# Main.net
KiCad netlist of a schematic drawn in Altium Designer
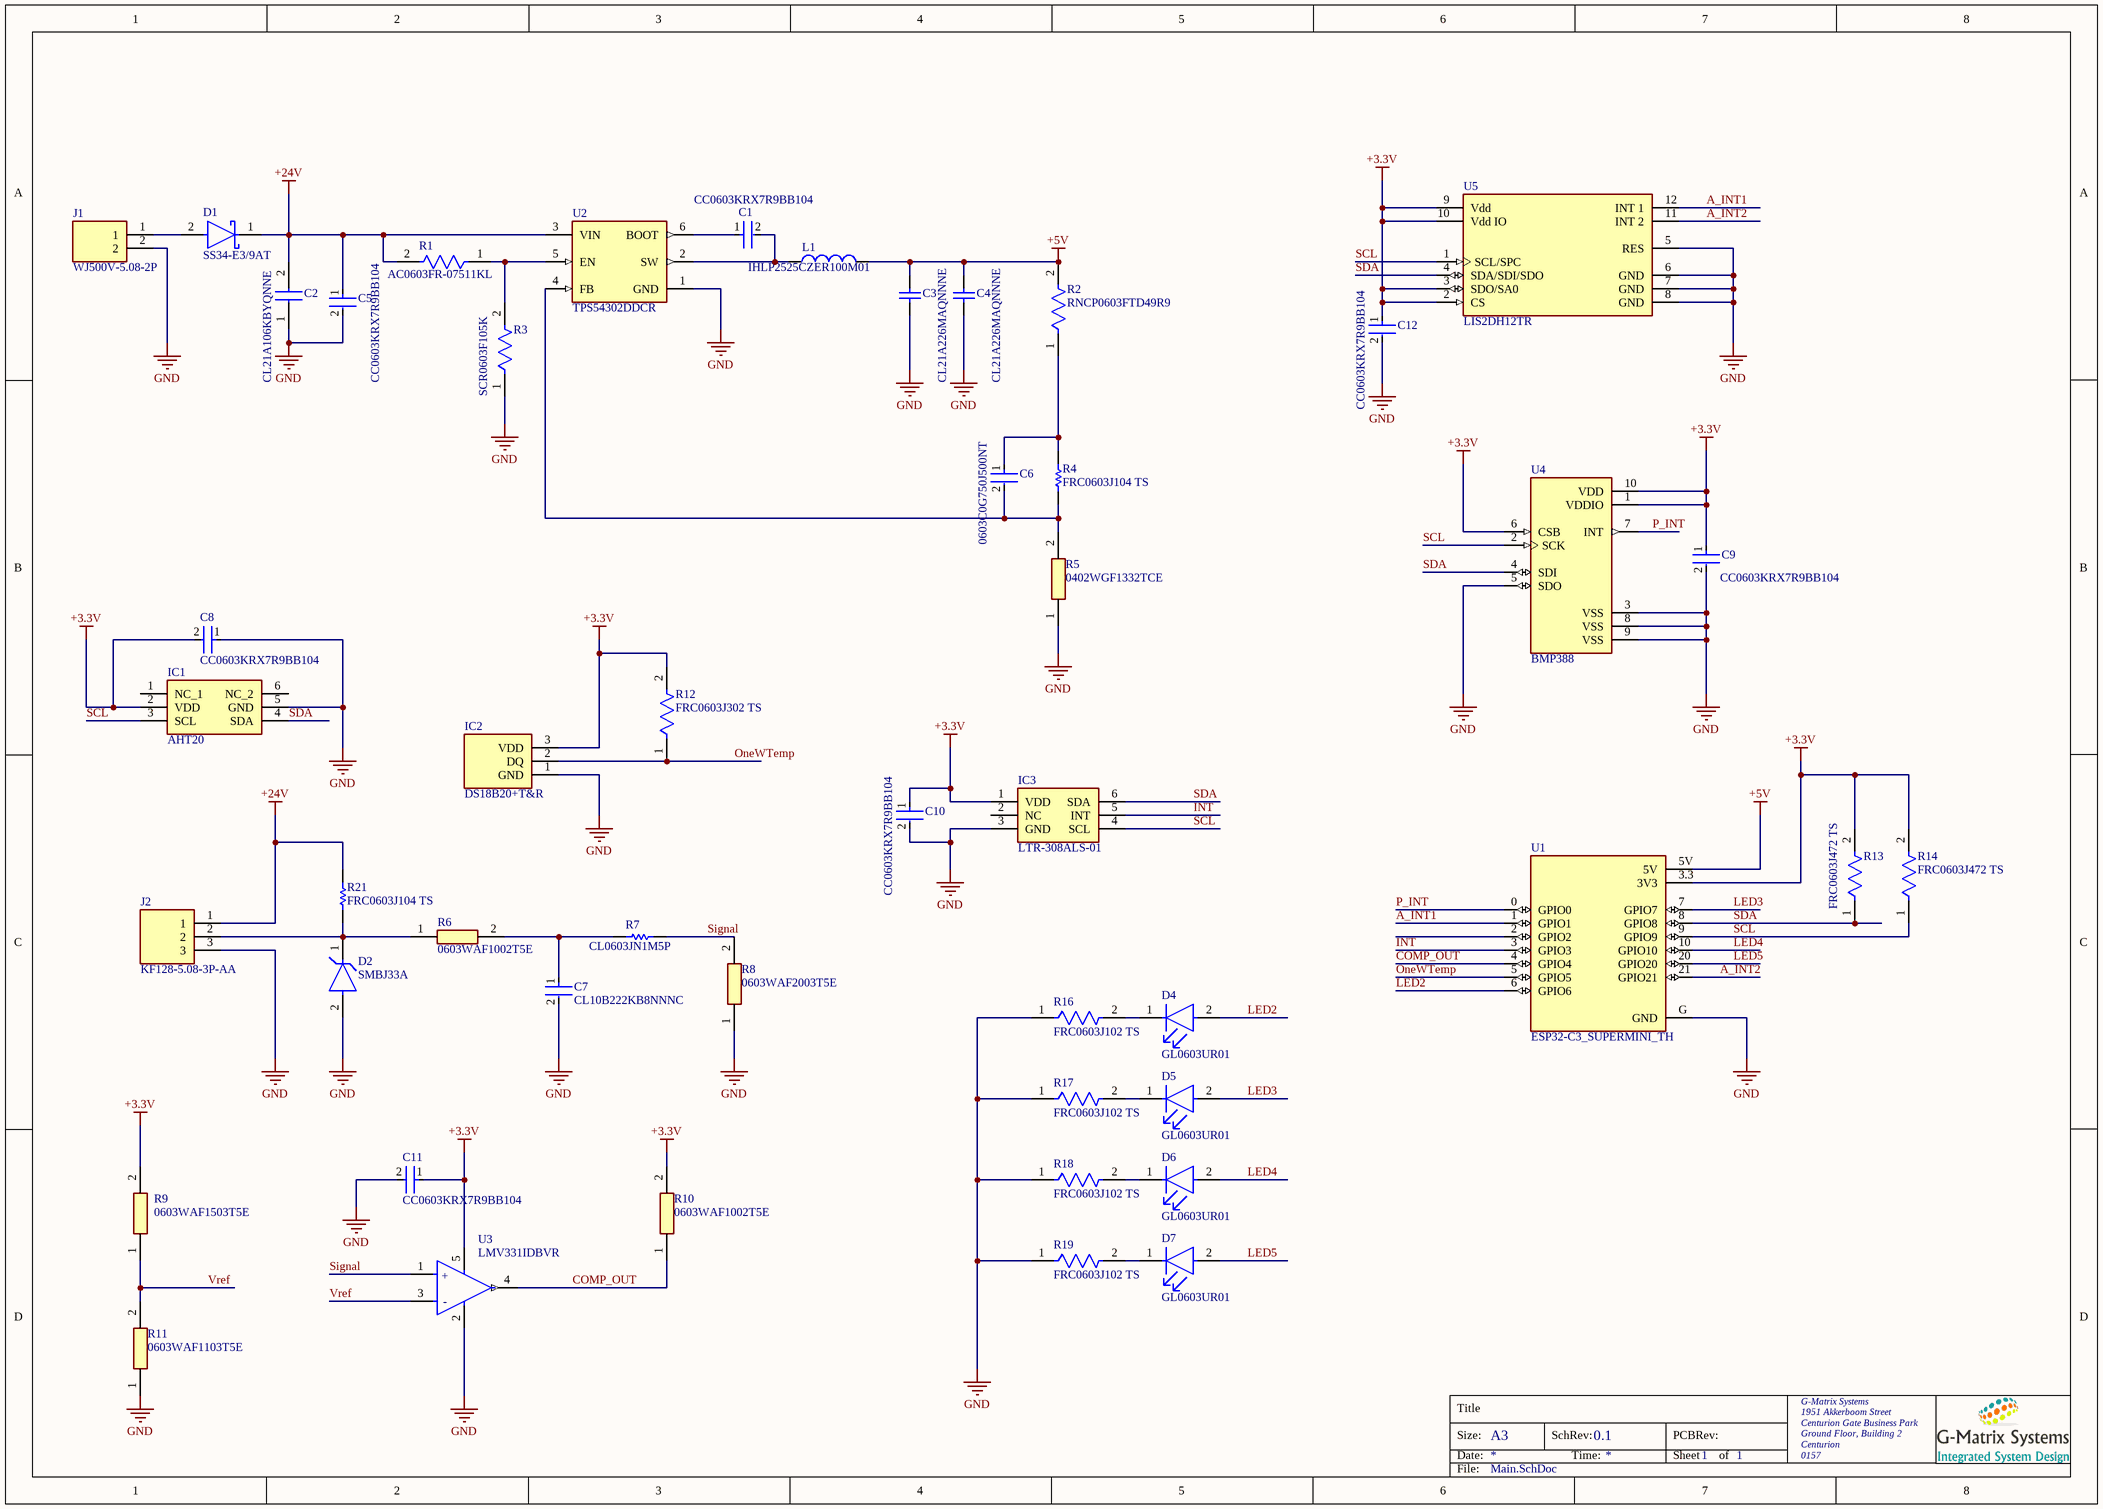
[diagram p0: Main.SchDoc]

(export (version "E")
  (design (tool "Eeschema 10.0.6"))
  (components
    (comp (ref "C1")
      (value "CC0603KRX7R9BB104")
      (footprint "FP-CC0603-DA-MFG")
      (description "CAP CER 0.1UF 50V X7R 0603")
      (fields (field (name "MANUFACTURER") "YAGEO") (field (name "VOLTAGE") "50 V"))
      (libsource (lib "Altium Content Vault") (part "11868f565c42a9108669ba33697ecf6"))
    )
    (comp (ref "C2")
      (value "CL21A106KBYQNNE")
      (footprint "SamacSys:CAPC2012X145N")
      (description "Capacitor")
      (fields (field (name "MOUSER PART NUMBER") "187-CL21A106KBYQNNE"))
      (libsource (lib "*") (part "CL21A106KBYQNNE"))
    )
    (comp (ref "C3")
      (value "CL21A226MAQNNNE")
      (footprint "CAPC2013X140X45LL15T25")
      (description "Multi-layer Ceramic Capacitor, 22 uF, -55 to 85 degC, 2-Pin SMD (0805), RoHS, Tape and Reel")
      (fields (field (name "MANUFACTURER") "Samsung Electro-Mechanics") (field (name "TOLERANCE") "±20%"))
      (libsource (lib "Altium Content Vault") (part "CAP-NP-2"))
    )
    (comp (ref "C4")
      (value "CL21A226MAQNNNE")
      (footprint "CAPC2013X140X45LL15T25")
      (description "Multi-layer Ceramic Capacitor, 22 uF, -55 to 85 degC, 2-Pin SMD (0805), RoHS, Tape and Reel")
      (fields (field (name "MANUFACTURER") "Samsung Electro-Mechanics") (field (name "TOLERANCE") "±20%"))
      (libsource (lib "Altium Content Vault") (part "CAP-NP-2"))
    )
    (comp (ref "C5")
      (value "CC0603KRX7R9BB104")
      (footprint "FP-CC0603-DA-MFG")
      (description "CAP CER 0.1UF 50V X7R 0603")
      (fields (field (name "MANUFACTURER") "YAGEO") (field (name "VOLTAGE") "50 V"))
      (libsource (lib "Altium Content Vault") (part "11868f565c42a9108669ba33697ecf6"))
    )
    (comp (ref "C6")
      (value "0603C0G750J500NT")
      (footprint "FP-CC0603-0_1-0_9-MFG")
      (description "CC0603FRNPO9BN750 Multilayer Ceramic Capacitor, 75 pF, 50 V, ± 1%, C0G (NP0), 0603 [1608 Metric]")
      (fields (field (name "TOLERANCE") "1%"))
      (libsource (lib "Altium Content Vault") (part "b4654b650e69147ec39a6b967a45e02"))
    )
    (comp (ref "C7")
      (value "CL10B222KB8NNNC")
      (footprint "FP-CL10-IPC_A")
      (description "Cap Ceramic 2.2nF 50V X7R ±10% Pad SMD 0603 +125°C T/R")
      (fields (field (name "VOLTAGE") "25V") (field (name "TOLERANCE") "10%"))
      (libsource (lib "Altium Content Vault") (part "b4654b650e69147ec39a6b967a45e02"))
    )
    (comp (ref "C8")
      (value "CC0603KRX7R9BB104")
      (footprint "FP-CC0603-DA-MFG")
      (description "CAP CER 0.1UF 50V X7R 0603")
      (fields (field (name "MANUFACTURER") "YAGEO") (field (name "VOLTAGE") "50 V"))
      (libsource (lib "Altium Content Vault") (part "11868f565c42a9108669ba33697ecf6"))
    )
    (comp (ref "C9")
      (value "CC0603KRX7R9BB104")
      (footprint "FP-CC0603-DA-MFG")
      (description "CAP CER 0.1UF 50V X7R 0603")
      (fields (field (name "MANUFACTURER") "YAGEO") (field (name "VOLTAGE") "50 V"))
      (libsource (lib "Altium Content Vault") (part "11868f565c42a9108669ba33697ecf6"))
    )
    (comp (ref "C10")
      (value "CC0603KRX7R9BB104")
      (footprint "FP-CC0603-DA-MFG")
      (description "CAP CER 0.1UF 50V X7R 0603")
      (fields (field (name "MANUFACTURER") "YAGEO") (field (name "VOLTAGE") "50 V"))
      (libsource (lib "Altium Content Vault") (part "11868f565c42a9108669ba33697ecf6"))
    )
    (comp (ref "C11")
      (value "CC0603KRX7R9BB104")
      (footprint "FP-CC0603-DA-MFG")
      (description "CAP CER 0.1UF 50V X7R 0603")
      (fields (field (name "MANUFACTURER") "YAGEO") (field (name "VOLTAGE") "50 V"))
      (libsource (lib "Altium Content Vault") (part "11868f565c42a9108669ba33697ecf6"))
    )
    (comp (ref "C12")
      (value "CC0603KRX7R9BB104")
      (footprint "FP-CC0603-DA-MFG")
      (description "CAP CER 0.1UF 50V X7R 0603")
      (fields (field (name "MANUFACTURER") "YAGEO") (field (name "VOLTAGE") "50 V"))
      (libsource (lib "Altium Content Vault") (part "11868f565c42a9108669ba33697ecf6"))
    )
    (comp (ref "D1")
      (value "SS34-E3/9AT")
      (footprint "FP-SMC-MFG")
      (description "DIODE SCHOTTKY 40V 3A DO214AB")
      (libsource (lib "Altium Content Vault") (part "c1678fac7984e62e0809fbf79c06691"))
    )
    (comp (ref "D2")
      (value "SMBJ33A")
      (footprint "FP-SMBJ-MFG")
      (description "TVS DIODE 33V 53.3V DO214AA")
      (fields
        (field (name "MANUFACTURER") "Littelfuse Inc")
        (field (name "OCTOPART") "https://octopart.com/smbj33a-littelfuse-350829")
      )
      (libsource (lib "Altium Content Vault") (part "f813f71cba58e380607f5dd3caf9714"))
    )
    (comp (ref "D4")
      (value "GL0603UR01")
      (footprint "FP-LSM0603453V-MFG")
      (description "LSM0603453V LED SM 0603 3V -/1000/-mcd Green")
      (libsource (lib "Altium Content Vault") (part "8706943c75ba83719d021d2fdc84c58"))
    )
    (comp (ref "D5")
      (value "GL0603UR01")
      (footprint "FP-LSM0603453V-MFG")
      (description "LSM0603453V LED SM 0603 3V -/1000/-mcd Green")
      (libsource (lib "Altium Content Vault") (part "8706943c75ba83719d021d2fdc84c58"))
    )
    (comp (ref "D6")
      (value "GL0603UR01")
      (footprint "FP-LSM0603453V-MFG")
      (description "LSM0603453V LED SM 0603 3V -/1000/-mcd Green")
      (libsource (lib "Altium Content Vault") (part "8706943c75ba83719d021d2fdc84c58"))
    )
    (comp (ref "D7")
      (value "GL0603UR01")
      (footprint "FP-LSM0603453V-MFG")
      (description "LSM0603453V LED SM 0603 3V -/1000/-mcd Green")
      (libsource (lib "Altium Content Vault") (part "8706943c75ba83719d021d2fdc84c58"))
    )
    (comp (ref "IC1")
      (value "AHT20")
      (footprint "SamacSys:AHT20")
      (description "Integrated Circuit")
      (libsource (lib "*") (part "AHT20"))
    )
    (comp (ref "IC2")
      (value "DS18B20+T&R")
      (footprint "SamacSys:DS18B20TR")
      (description "Integrated Circuit")
      (fields (field (name "MOUSER PART NUMBER") "700-DS18B20T&R"))
      (libsource (lib "*") (part "DS18B20+T&R"))
    )
    (comp (ref "IC3")
      (value "LTR-308ALS-01")
      (footprint "SamacSys:LTR303ALS01")
      (description "Integrated Circuit")
      (libsource (lib "*") (part "LTR-308ALS-01"))
    )
    (comp (ref "J1")
      (value "WJ500V-5.08-2P")
      (footprint "WJ500V5082P")
      (description "Connector")
      (libsource (lib "Mag") (part "WJ500V-5.08-2P"))
    )
    (comp (ref "J2")
      (value "KF128-5.08-3P-AA")
      (footprint "KF1285083PAA")
      (description "Connector")
      (libsource (lib "Mag") (part "KF128-5.08-3P-AA"))
    )
    (comp (ref "L1")
      (value "IHLP2525CZER100M01")
      (footprint "VISH-IHLP2525C-01_V")
      (fields (field (name "MANUFACTURER") "Vishay") (field (name "TOLERANCE") "20%"))
      (libsource (lib "Altium Content Vault") (part "IND-2"))
    )
    (comp (ref "R1")
      (value "AC0603FR-07511KL")
      (footprint "FP-AC0603-MFG")
      (description "RES 511KΩ 1.00% 0.1W 0603")
      (fields (field (name "TOLERANCE") "1%"))
      (libsource (lib "Altium Content Vault") (part "1029c3af85768c4190bb7ad29bc67b5"))
    )
    (comp (ref "R2")
      (value "RNCP0603FTD49R9")
      (footprint "FP-RNCP0603-IPC_C")
      (description "49.9Ω ±1% 0.125W 0603 High Power Anti-Sulfur Thin Film Chip Resistor")
      (fields (field (name "TOLERANCE") "1%"))
      (libsource (lib "Altium Content Vault") (part "1029c3af85768c4190bb7ad29bc67b5"))
    )
    (comp (ref "R3")
      (value "SCR0603F105K")
      (footprint "FP-CPF0603-MFG")
      (description "RES SMD 105KΩ 1% 1/16W 0603")
      (fields
        (field (name "TOLERANCE") "1%")
        (field (name "OCTOPART") "https://octopart.com/cpf0603f105kc1-te+connectivity-7514804")
      )
      (libsource (lib "Altium Content Vault") (part "1029c3af85768c4190bb7ad29bc67b5"))
    )
    (comp (ref "R4")
      (value "FRC0603J104 TS")
      (footprint "RESC0603(1608)_N")
      (description "100K 0.1W 1% 0603 (1608 Metric)  SMD")
      (fields (field (name "POWER") "0.1 W") (field (name "TOLERANCE") "1 %"))
      (libsource (lib "Altium Content Vault") (part "RES"))
    )
    (comp (ref "R5")
      (value "0402WGF1332TCE")
      (footprint "SamacSys:RESC1005X40N")
      (description "Resistor")
      (libsource (lib "*") (part "0402WGF1332TCE"))
    )
    (comp (ref "R6")
      (value "0603WAF1002T5E")
      (footprint "SamacSys:RESC1608X55N")
      (description "Resistor")
      (fields (field (name "MOUSER PART NUMBER") "303-0603WAF1002T5E"))
      (libsource (lib "*") (part "0603WAF1002T5E"))
    )
    (comp (ref "R7")
      (value "CL0603JN1M5P")
      (footprint "RESC0603(1608)_N")
      (description "1M5 0.1W 5% 0603 (1608 Metric)  SMD")
      (fields (field (name "TOLERANCE") "5 %") (field (name "POWER") "0.1 W"))
      (libsource (lib "Altium Content Vault") (part "RES"))
    )
    (comp (ref "R8")
      (value "0603WAF2003T5E")
      (footprint "SamacSys:RESC1608X55N")
      (description "Resistor")
      (libsource (lib "*") (part "0603WAF2003T5E"))
    )
    (comp (ref "R9")
      (value "0603WAF1503T5E")
      (footprint "SamacSys:RESC1608X55N")
      (description "Resistor")
      (libsource (lib "*") (part "0603WAF1503T5E"))
    )
    (comp (ref "R10")
      (value "0603WAF1002T5E")
      (footprint "SamacSys:RESC1608X55N")
      (description "Resistor")
      (fields (field (name "MOUSER PART NUMBER") "303-0603WAF1002T5E"))
      (libsource (lib "") (part "0603WAF1002T5E_1"))
    )
    (comp (ref "R11")
      (value "0603WAF1103T5E")
      (footprint "SamacSys:RESC1608X55N")
      (description "Resistor")
      (libsource (lib "*") (part "0603WAF1103T5E"))
    )
    (comp (ref "R12")
      (value "FRC0603J302 TS")
      (footprint "FP-ESR03-IPC_A")
      (description "3kΩ ±5% 0.25W 0603 Anti-Surge Chip Resistor AEC-Q200")
      (fields (field (name "TOLERANCE") "5%"))
      (libsource (lib "Altium Content Vault") (part "1029c3af85768c4190bb7ad29bc67b5"))
    )
    (comp (ref "R13")
      (value "FRC0603J472 TS")
      (footprint "FP-MCT0603-IPC_C")
      (description "RES SMD 100 OHM 1% 1/8W 0603")
      (libsource (lib "Altium Content Vault") (part "1029c3af85768c4190bb7ad29bc67b5"))
    )
    (comp (ref "R14")
      (value "FRC0603J472 TS")
      (footprint "FP-MCT0603-IPC_C")
      (description "RES SMD 100 OHM 1% 1/8W 0603")
      (libsource (lib "Altium Content Vault") (part "1029c3af85768c4190bb7ad29bc67b5"))
    )
    (comp (ref "R16")
      (value "FRC0603J102 TS")
      (footprint "FP-TFCR0603-MFG")
      (description "RES Thin Film,  1kΩ, 1%, 0.1W, 25ppm/°C, 0603")
      (libsource (lib "Altium Content Vault") (part "1029c3af85768c4190bb7ad29bc67b5"))
    )
    (comp (ref "R17")
      (value "FRC0603J102 TS")
      (footprint "FP-TFCR0603-MFG")
      (description "RES Thin Film,  1kΩ, 1%, 0.1W, 25ppm/°C, 0603")
      (libsource (lib "Altium Content Vault") (part "1029c3af85768c4190bb7ad29bc67b5"))
    )
    (comp (ref "R18")
      (value "FRC0603J102 TS")
      (footprint "FP-TFCR0603-MFG")
      (description "RES Thin Film,  1kΩ, 1%, 0.1W, 25ppm/°C, 0603")
      (libsource (lib "Altium Content Vault") (part "1029c3af85768c4190bb7ad29bc67b5"))
    )
    (comp (ref "R19")
      (value "FRC0603J102 TS")
      (footprint "FP-TFCR0603-MFG")
      (description "RES Thin Film,  1kΩ, 1%, 0.1W, 25ppm/°C, 0603")
      (libsource (lib "Altium Content Vault") (part "1029c3af85768c4190bb7ad29bc67b5"))
    )
    (comp (ref "R21")
      (value "FRC0603J104 TS")
      (footprint "RESC0603(1608)_N")
      (description "100K 0.1W 1% 0603 (1608 Metric)  SMD")
      (fields (field (name "POWER") "0.1 W") (field (name "TOLERANCE") "1 %"))
      (libsource (lib "Altium Content Vault") (part "RES"))
    )
    (comp (ref "U1")
      (value "ESP32-C3_SUPERMINI_TH")
      (footprint "MODULE_ESP32-C3_SUPERMINI_TH")
      (description "Super tiny ESP32-C3 board")
      (fields (field (name "MF") "Espressif Systems") (field (name "MP") "ESP32-C3 SuperMini_TH"))
      (libsource (lib "Mag") (part "ESP32-C3_SUPERMINI_TH"))
    )
    (comp (ref "U2")
      (value "TPS54302DDCR")
      (footprint "FP-DDC0006A-MFG")
      (description "IC REG BUCK ADJ 3A TSOT23-6")
      (fields
        (field (name "MANUFACTURER") "Texas Instruments")
        (field (name "OCTOPART") "https://octopart.com/tps54302ddcr-texas+instruments-74209025")
      )
      (libsource (lib "Altium Content Vault") (part "e6e62595b56d4ede9a2c24ebe42f01f"))
    )
    (comp (ref "U3")
      (value "LMV331IDBVR")
      (footprint "FP-DBV0005A-MFG")
      (description "IC GP LV COMPARATOR SOT-23-5")
      (fields
        (field (name "MANUFACTURER") "Texas Instruments")
        (field (name "OCTOPART") "https://octopart.com/lmv331idbvr-texas+instruments-428444")
      )
      (libsource (lib "Altium Content Vault") (part "5966c262b33e2942c4899dda8c5e135"))
    )
    (comp (ref "U4")
      (value "BMP388")
      (footprint "PQFN50P200X200X80-10N")
      (description "P-Sensor SPI I2C 1, 25 Bar SMD")
      (libsource (lib "G-Matrix Systems") (part "BMP388"))
    )
    (comp (ref "U5")
      (value "LIS2DH12TR")
      (footprint "FP-LGA-12-8365767-MFG")
      (description "ACCEL 2-16G I2C/SPI 12LGA")
      (libsource (lib "Altium Content Vault") (part "43ad9b989a05401887db1079274fe63"))
    )
  )
  (nets
    (net (code "1") (name "+3.3V") (class "Default")
      (node (ref "C10") (pin "1") (pinfunction "1_1") (pintype "passive"))
      (node (ref "C11") (pin "1") (pinfunction "1_1") (pintype "passive"))
      (node (ref "C12") (pin "1") (pinfunction "1_1") (pintype "passive"))
      (node (ref "C8") (pin "2") (pinfunction "2_2") (pintype "passive"))
      (node (ref "C9") (pin "1") (pinfunction "1_1") (pintype "passive"))
      (node (ref "IC1") (pin "2") (pinfunction "VDD_2") (pintype "passive"))
      (node (ref "IC2") (pin "3") (pinfunction "VDD_3") (pintype "passive"))
      (node (ref "IC3") (pin "1") (pinfunction "VDD_1") (pintype "passive"))
      (node (ref "R10") (pin "2") (pinfunction "2_2") (pintype "passive"))
      (node (ref "R12") (pin "2") (pinfunction "2_2") (pintype "passive"))
      (node (ref "R13") (pin "2") (pinfunction "2_2") (pintype "passive"))
      (node (ref "R14") (pin "2") (pinfunction "2_2") (pintype "passive"))
      (node (ref "R9") (pin "2") (pinfunction "2_2") (pintype "passive"))
      (node (ref "U1") (pin "3.3") (pinfunction "3V3_3.3") (pintype "power_in"))
      (node (ref "U3") (pin "5") (pinfunction "VCC+_5") (pintype "power_in"))
      (node (ref "U4") (pin "1") (pinfunction "VDDIO_1") (pintype "power_in"))
      (node (ref "U4") (pin "10") (pinfunction "VDD_10") (pintype "power_in"))
      (node (ref "U4") (pin "6") (pinfunction "CSB_6") (pintype "input"))
      (node (ref "U5") (pin "10") (pinfunction "Vdd_IO_10") (pintype "power_in"))
      (node (ref "U5") (pin "2") (pinfunction "CS_2") (pintype "input"))
      (node (ref "U5") (pin "3") (pinfunction "SDO/SA0_3") (pintype "bidirectional"))
      (node (ref "U5") (pin "9") (pinfunction "Vdd_9") (pintype "power_in"))
    )
    (net (code "2") (name "+5V") (class "Default")
      (node (ref "C3") (pin "2") (pinfunction "2_2") (pintype "passive"))
      (node (ref "C4") (pin "2") (pinfunction "2_2") (pintype "passive"))
      (node (ref "L1") (pin "2") (pinfunction "2_2") (pintype "passive"))
      (node (ref "R2") (pin "2") (pinfunction "2_2") (pintype "passive"))
      (node (ref "U1") (pin "5V") (pinfunction "5V_5V") (pintype "power_in"))
    )
    (net (code "3") (name "+24V") (class "Default")
      (node (ref "C2") (pin "2") (pinfunction "2_2") (pintype "passive"))
      (node (ref "C5") (pin "1") (pinfunction "1_1") (pintype "passive"))
      (node (ref "D1") (pin "1") (pinfunction "C_1") (pintype "passive"))
      (node (ref "J2") (pin "1") (pinfunction "1_1") (pintype "passive"))
      (node (ref "R1") (pin "2") (pinfunction "2_2") (pintype "passive"))
      (node (ref "R21") (pin "2") (pinfunction "2_2") (pintype "passive"))
      (node (ref "U2") (pin "3") (pinfunction "VIN_3") (pintype "power_in"))
    )
    (net (code "4") (name "/A_INT1") (class "Default")
      (node (ref "U1") (pin "1") (pinfunction "GPIO1_1") (pintype "bidirectional"))
      (node (ref "U5") (pin "12") (pinfunction "INT_1_12") (pintype "passive"))
    )
    (net (code "5") (name "/A_INT2") (class "Default")
      (node (ref "U1") (pin "21") (pinfunction "GPIO21_21") (pintype "bidirectional"))
      (node (ref "U5") (pin "11") (pinfunction "INT_2_11") (pintype "passive"))
    )
    (net (code "6") (name "/COMP_OUT") (class "Default")
      (node (ref "R10") (pin "1") (pinfunction "1_1") (pintype "passive"))
      (node (ref "U1") (pin "4") (pinfunction "GPIO4_4") (pintype "bidirectional"))
      (node (ref "U3") (pin "4") (pinfunction "OUT_4") (pintype "output"))
    )
    (net (code "7") (name "/INT") (class "Default")
      (node (ref "IC3") (pin "5") (pinfunction "INT_5") (pintype "passive"))
      (node (ref "U1") (pin "3") (pinfunction "GPIO3_3") (pintype "bidirectional"))
    )
    (net (code "8") (name "/LED2") (class "Default")
      (node (ref "D4") (pin "2") (pinfunction "A_2") (pintype "passive"))
      (node (ref "U1") (pin "6") (pinfunction "GPIO6_6") (pintype "bidirectional"))
    )
    (net (code "9") (name "/LED3") (class "Default")
      (node (ref "D5") (pin "2") (pinfunction "A_2") (pintype "passive"))
      (node (ref "U1") (pin "7") (pinfunction "GPIO7_7") (pintype "bidirectional"))
    )
    (net (code "10") (name "/LED4") (class "Default")
      (node (ref "D6") (pin "2") (pinfunction "A_2") (pintype "passive"))
      (node (ref "U1") (pin "10") (pinfunction "GPIO10_10") (pintype "bidirectional"))
    )
    (net (code "11") (name "/LED5") (class "Default")
      (node (ref "D7") (pin "2") (pinfunction "A_2") (pintype "passive"))
      (node (ref "U1") (pin "20") (pinfunction "GPIO20_20") (pintype "bidirectional"))
    )
    (net (code "12") (name "/OneWTemp") (class "Default")
      (node (ref "IC2") (pin "2") (pinfunction "DQ_2") (pintype "passive"))
      (node (ref "R12") (pin "1") (pinfunction "1_1") (pintype "passive"))
      (node (ref "U1") (pin "5") (pinfunction "GPIO5_5") (pintype "bidirectional"))
    )
    (net (code "13") (name "/P_INT") (class "Default")
      (node (ref "U1") (pin "0") (pinfunction "GPIO0_0") (pintype "bidirectional"))
      (node (ref "U4") (pin "7") (pinfunction "INT_7") (pintype "output"))
    )
    (net (code "14") (name "/SCL") (class "Default")
      (node (ref "IC1") (pin "3") (pinfunction "SCL_3") (pintype "passive"))
      (node (ref "IC3") (pin "4") (pinfunction "SCL_4") (pintype "passive"))
      (node (ref "R14") (pin "1") (pinfunction "1_1") (pintype "passive"))
      (node (ref "U1") (pin "9") (pinfunction "GPIO9_9") (pintype "bidirectional"))
      (node (ref "U4") (pin "2") (pinfunction "SCK_2") (pintype "input"))
      (node (ref "U5") (pin "1") (pinfunction "SCL/SPC_1") (pintype "input"))
    )
    (net (code "15") (name "/SDA") (class "Default")
      (node (ref "IC1") (pin "4") (pinfunction "SDA_4") (pintype "passive"))
      (node (ref "IC3") (pin "6") (pinfunction "SDA_6") (pintype "passive"))
      (node (ref "R13") (pin "1") (pinfunction "1_1") (pintype "passive"))
      (node (ref "U1") (pin "8") (pinfunction "GPIO8_8") (pintype "bidirectional"))
      (node (ref "U4") (pin "4") (pinfunction "SDI_4") (pintype "bidirectional"))
      (node (ref "U5") (pin "4") (pinfunction "SDA/SDI/SDO_4") (pintype "bidirectional"))
    )
    (net (code "16") (name "/Signal") (class "Default")
      (node (ref "R7") (pin "1") (pinfunction "1_1") (pintype "passive"))
      (node (ref "R8") (pin "2") (pinfunction "2_2") (pintype "passive"))
      (node (ref "U3") (pin "1") (pinfunction "1IN+_1") (pintype "tri_state"))
    )
    (net (code "17") (name "/Vref") (class "Default")
      (node (ref "R11") (pin "2") (pinfunction "2_2") (pintype "passive"))
      (node (ref "R9") (pin "1") (pinfunction "1_1") (pintype "passive"))
      (node (ref "U3") (pin "3") (pinfunction "1IN-_3") (pintype "tri_state"))
    )
    (net (code "18") (name "GND") (class "Default")
      (node (ref "C10") (pin "2") (pinfunction "2_2") (pintype "passive"))
      (node (ref "C11") (pin "2") (pinfunction "2_2") (pintype "passive"))
      (node (ref "C12") (pin "2") (pinfunction "2_2") (pintype "passive"))
      (node (ref "C2") (pin "1") (pinfunction "1_1") (pintype "passive"))
      (node (ref "C3") (pin "1") (pinfunction "1_1") (pintype "passive"))
      (node (ref "C4") (pin "1") (pinfunction "1_1") (pintype "passive"))
      (node (ref "C5") (pin "2") (pinfunction "2_2") (pintype "passive"))
      (node (ref "C7") (pin "2") (pinfunction "2_2") (pintype "passive"))
      (node (ref "C8") (pin "1") (pinfunction "1_1") (pintype "passive"))
      (node (ref "C9") (pin "2") (pinfunction "2_2") (pintype "passive"))
      (node (ref "D2") (pin "2") (pinfunction "A_2") (pintype "passive"))
      (node (ref "IC1") (pin "5") (pinfunction "GND_5") (pintype "passive"))
      (node (ref "IC2") (pin "1") (pinfunction "GND_1") (pintype "passive"))
      (node (ref "IC3") (pin "3") (pinfunction "GND_3") (pintype "passive"))
      (node (ref "J1") (pin "2") (pinfunction "2_2") (pintype "passive"))
      (node (ref "J2") (pin "3") (pinfunction "3_3") (pintype "passive"))
      (node (ref "R11") (pin "1") (pinfunction "1_1") (pintype "passive"))
      (node (ref "R16") (pin "1") (pinfunction "1_1") (pintype "passive"))
      (node (ref "R17") (pin "1") (pinfunction "1_1") (pintype "passive"))
      (node (ref "R18") (pin "1") (pinfunction "1_1") (pintype "passive"))
      (node (ref "R19") (pin "1") (pinfunction "1_1") (pintype "passive"))
      (node (ref "R3") (pin "1") (pinfunction "1_1") (pintype "passive"))
      (node (ref "R5") (pin "1") (pinfunction "1_1") (pintype "passive"))
      (node (ref "R8") (pin "1") (pinfunction "1_1") (pintype "passive"))
      (node (ref "U1") (pin "G") (pinfunction "GND_G") (pintype "power_in"))
      (node (ref "U2") (pin "1") (pinfunction "GND_1") (pintype "power_in"))
      (node (ref "U3") (pin "2") (pinfunction "GND_2") (pintype "power_in"))
      (node (ref "U4") (pin "3") (pinfunction "VSS_3") (pintype "power_in"))
      (node (ref "U4") (pin "5") (pinfunction "SDO_5") (pintype "bidirectional"))
      (node (ref "U4") (pin "8") (pinfunction "VSS_8") (pintype "power_in"))
      (node (ref "U4") (pin "9") (pinfunction "VSS_9") (pintype "power_in"))
      (node (ref "U5") (pin "5") (pinfunction "RES_5") (pintype "power_in"))
      (node (ref "U5") (pin "6") (pinfunction "GND_6") (pintype "power_in"))
      (node (ref "U5") (pin "7") (pinfunction "GND_7") (pintype "power_in"))
      (node (ref "U5") (pin "8") (pinfunction "GND_8") (pintype "power_in"))
    )
    (net (code "19") (name "Net-(C6-Pad1)") (class "Default")
      (node (ref "C6") (pin "1") (pinfunction "1_1") (pintype "passive"))
      (node (ref "R2") (pin "1") (pinfunction "1_1") (pintype "passive"))
      (node (ref "R4") (pin "2") (pinfunction "2_2") (pintype "passive"))
    )
    (net (code "20") (name "Net-(C7-Pad1)") (class "Default")
      (node (ref "C7") (pin "1") (pinfunction "1_1") (pintype "passive"))
      (node (ref "R6") (pin "2") (pinfunction "2_2") (pintype "passive"))
      (node (ref "R7") (pin "2") (pinfunction "2_2") (pintype "passive"))
    )
    (net (code "21") (name "Net-(D1-A)") (class "Default")
      (node (ref "D1") (pin "2") (pinfunction "A_2") (pintype "passive"))
      (node (ref "J1") (pin "1") (pinfunction "1_1") (pintype "passive"))
    )
    (net (code "22") (name "Net-(D2-C)") (class "Default")
      (node (ref "D2") (pin "1") (pinfunction "C_1") (pintype "passive"))
      (node (ref "J2") (pin "2") (pinfunction "2_2") (pintype "passive"))
      (node (ref "R21") (pin "1") (pinfunction "1_1") (pintype "passive"))
      (node (ref "R6") (pin "1") (pinfunction "1_1") (pintype "passive"))
    )
    (net (code "23") (name "Net-(D4-C)") (class "Default")
      (node (ref "D4") (pin "1") (pinfunction "C_1") (pintype "passive"))
      (node (ref "R16") (pin "2") (pinfunction "2_2") (pintype "passive"))
    )
    (net (code "24") (name "Net-(D5-C)") (class "Default")
      (node (ref "D5") (pin "1") (pinfunction "C_1") (pintype "passive"))
      (node (ref "R17") (pin "2") (pinfunction "2_2") (pintype "passive"))
    )
    (net (code "25") (name "Net-(D6-C)") (class "Default")
      (node (ref "D6") (pin "1") (pinfunction "C_1") (pintype "passive"))
      (node (ref "R18") (pin "2") (pinfunction "2_2") (pintype "passive"))
    )
    (net (code "26") (name "Net-(D7-C)") (class "Default")
      (node (ref "D7") (pin "1") (pinfunction "C_1") (pintype "passive"))
      (node (ref "R19") (pin "2") (pinfunction "2_2") (pintype "passive"))
    )
    (net (code "27") (name "Net-(U2-BOOT)") (class "Default")
      (node (ref "C1") (pin "1") (pinfunction "1_1") (pintype "passive"))
      (node (ref "U2") (pin "6") (pinfunction "BOOT_6") (pintype "output"))
    )
    (net (code "28") (name "Net-(U2-EN)") (class "Default")
      (node (ref "R1") (pin "1") (pinfunction "1_1") (pintype "passive"))
      (node (ref "R3") (pin "2") (pinfunction "2_2") (pintype "passive"))
      (node (ref "U2") (pin "5") (pinfunction "EN_5") (pintype "input"))
    )
    (net (code "29") (name "Net-(U2-FB)") (class "Default")
      (node (ref "C6") (pin "2") (pinfunction "2_2") (pintype "passive"))
      (node (ref "R4") (pin "1") (pinfunction "1_1") (pintype "passive"))
      (node (ref "R5") (pin "2") (pinfunction "2_2") (pintype "passive"))
      (node (ref "U2") (pin "4") (pinfunction "FB_4") (pintype "input"))
    )
    (net (code "30") (name "Net-(U2-SW)") (class "Default")
      (node (ref "C1") (pin "2") (pinfunction "2_2") (pintype "passive"))
      (node (ref "L1") (pin "1") (pinfunction "1_1") (pintype "passive"))
      (node (ref "U2") (pin "2") (pinfunction "SW_2") (pintype "output"))
    )
    (net (code "31") (name "unconnected-(IC1-NC_1-Pad1)") (class "Default")
      (node (ref "IC1") (pin "1") (pinfunction "NC_1_1") (pintype "passive"))
    )
    (net (code "32") (name "unconnected-(IC1-NC_2-Pad6)") (class "Default")
      (node (ref "IC1") (pin "6") (pinfunction "NC_2_6") (pintype "passive"))
    )
    (net (code "33") (name "unconnected-(IC3-NC-Pad2)") (class "Default")
      (node (ref "IC3") (pin "2") (pinfunction "NC_2") (pintype "passive"))
    )
    (net (code "34") (name "unconnected-(U1-GPIO2-Pad2)") (class "Default")
      (node (ref "U1") (pin "2") (pinfunction "GPIO2_2") (pintype "bidirectional"))
    )
  )
)
